# IRDA-piHAT.net
KiCad netlist of a schematic drawn in EAGLE
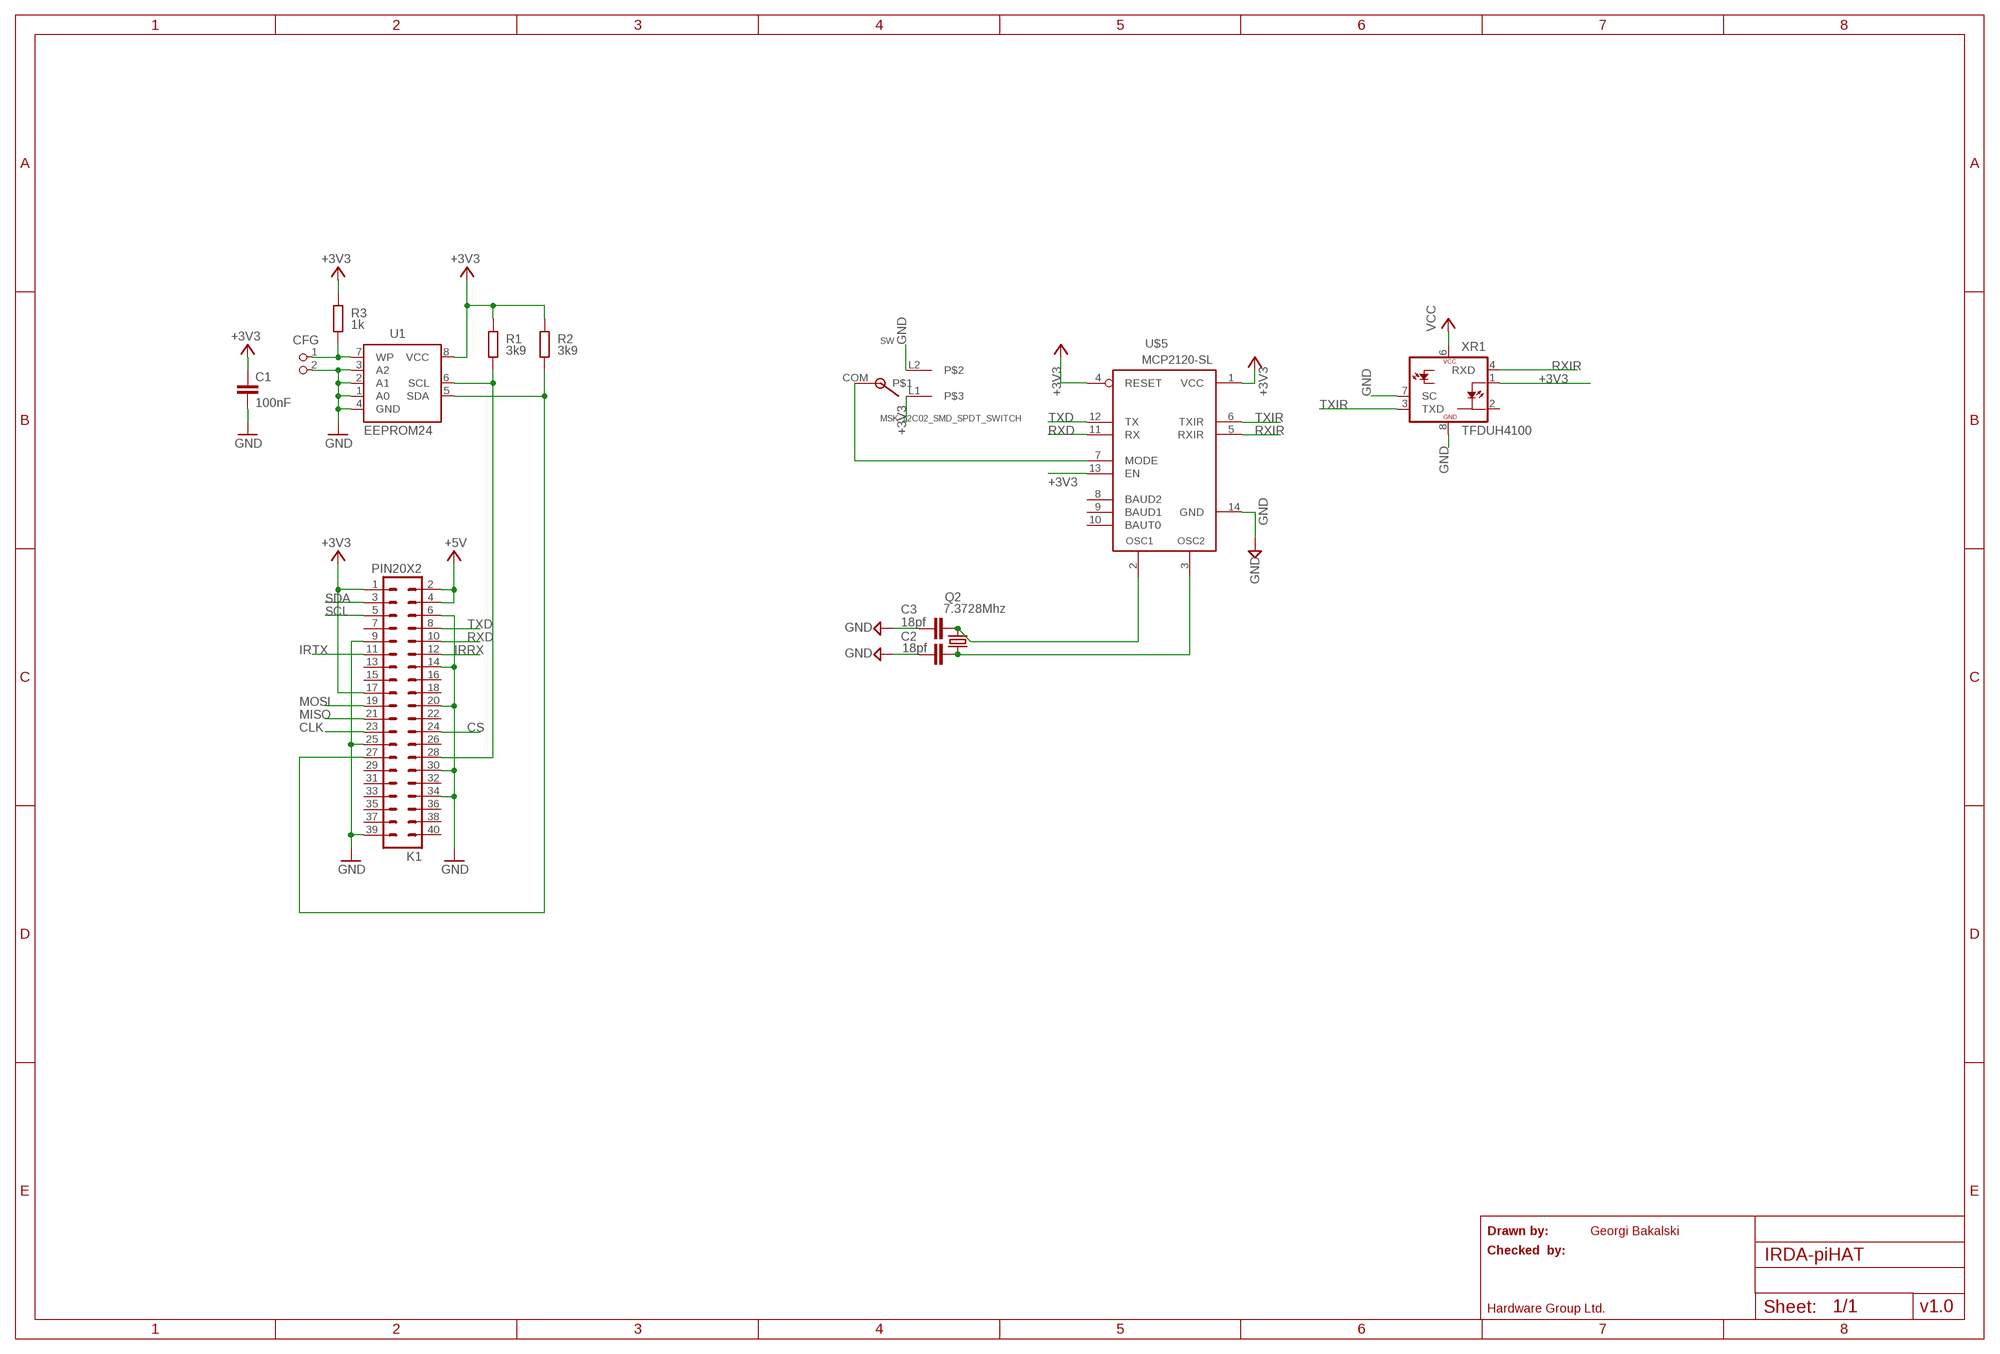
[diagram p0: schematic, sheet 1]

(export (version "E")
  (design (tool "Eeschema 10.0.6"))
  (components
    (comp (ref "C1")
      (value "100nF")
      (footprint "eagle-import:C0805K")
      (libsource (lib "eagle-import") (part "C-EUC0805K"))
    )
    (comp (ref "C2")
      (value "18pf")
      (footprint "eagle-import:C603")
      (libsource (lib "eagle-import") (part "CAPC603"))
    )
    (comp (ref "C3")
      (value "18pf")
      (footprint "eagle-import:C603")
      (libsource (lib "eagle-import") (part "CAPC603"))
    )
    (comp (ref "CFG")
      (value "PIN2_100")
      (footprint "eagle-import:PIN_W_2")
      (libsource (lib "eagle-import") (part "PIN2_100"))
    )
    (comp (ref "K1")
      (value "PIN20X2")
      (footprint "eagle-import:PIN_20X2")
      (libsource (lib "eagle-import") (part "PIN20X2"))
    )
    (comp (ref "Q2")
      (value "7.3728Mhz")
      (footprint "eagle-import:HC49UP")
      (libsource (lib "eagle-import") (part "CRYSTALHC49UP"))
    )
    (comp (ref "R1")
      (value "3k9")
      (footprint "eagle-import:M0805")
      (fields (field (name "TOLERANCE") "5%"))
      (libsource (lib "eagle-import") (part "R-EU_M0805"))
    )
    (comp (ref "R2")
      (value "3k9")
      (footprint "eagle-import:M0805")
      (fields (field (name "TOLERANCE") "5%"))
      (libsource (lib "eagle-import") (part "R-EU_M0805"))
    )
    (comp (ref "R3")
      (value "1k")
      (footprint "eagle-import:M0805")
      (fields (field (name "TOLERANCE") "5%"))
      (libsource (lib "eagle-import") (part "R-EU_M0805"))
    )
    (comp (ref "SW")
      (value "MSK-12C02_SMD_SPDT_SWITCH")
      (footprint "eagle-import:MSK-12C02")
      (libsource (lib "eagle-import") (part "MSK-12C02_SMD_SPDT_SWITCH"))
    )
    (comp (ref "U$5")
      (value "MCP2120-SL")
      (footprint "eagle-import:SO-14")
      (libsource (lib "eagle-import") (part "MCP2120-SL"))
    )
    (comp (ref "U1")
      (value "EEPROM24")
      (footprint "eagle-import:SOIC8")
      (libsource (lib "eagle-import") (part "EEPROM24"))
    )
    (comp (ref "XR1")
      (value "TFDUH4100")
      (footprint "eagle-import:TFDU4-HOR")
      (fields (field (name "MPN") "TFDU4101-TT3"))
      (libsource (lib "eagle-import") (part "TFD?4100UH"))
    )
  )
  (nets
    (net (code "1") (name "+3V3") (class "Default")
      (node (ref "C1") (pin "1") (pinfunction "1_1") (pintype "passive"))
      (node (ref "K1") (pin "1") (pinfunction "1_1") (pintype "passive"))
      (node (ref "K1") (pin "17") (pinfunction "17_17") (pintype "passive"))
      (node (ref "R1") (pin "2") (pinfunction "2_2") (pintype "passive"))
      (node (ref "R2") (pin "2") (pinfunction "2_2") (pintype "passive"))
      (node (ref "R3") (pin "2") (pinfunction "2_2") (pintype "passive"))
      (node (ref "SW") (pin "L1") (pinfunction "P$3_L1") (pintype "bidirectional"))
      (node (ref "U$5") (pin "1") (pinfunction "VCC_1") (pintype "power_in"))
      (node (ref "U$5") (pin "13") (pinfunction "EN_13") (pintype "input"))
      (node (ref "U$5") (pin "4") (pinfunction "RESET_4") (pintype "bidirectional"))
      (node (ref "U1") (pin "8") (pinfunction "VCC_8") (pintype "power_in"))
      (node (ref "XR1") (pin "1") (pinfunction "IRED-A_1") (pintype "passive"))
      (node (ref "XR1") (pin "6") (pinfunction "VCC_6") (pintype "power_in"))
    )
    (net (code "2") (name "+5V") (class "Default")
      (node (ref "K1") (pin "2") (pinfunction "2_2") (pintype "passive"))
      (node (ref "K1") (pin "4") (pinfunction "4_4") (pintype "passive"))
    )
    (net (code "3") (name "/CLK") (class "Default")
      (node (ref "K1") (pin "23") (pinfunction "23_23") (pintype "passive"))
    )
    (net (code "4") (name "/CS") (class "Default")
      (node (ref "K1") (pin "24") (pinfunction "24_24") (pintype "passive"))
    )
    (net (code "5") (name "/IRRX") (class "Default")
      (node (ref "K1") (pin "12") (pinfunction "12_12") (pintype "passive"))
    )
    (net (code "6") (name "/IRTX") (class "Default")
      (node (ref "K1") (pin "11") (pinfunction "11_11") (pintype "passive"))
    )
    (net (code "7") (name "/MISO") (class "Default")
      (node (ref "K1") (pin "21") (pinfunction "21_21") (pintype "passive"))
    )
    (net (code "8") (name "/MOSI") (class "Default")
      (node (ref "K1") (pin "19") (pinfunction "19_19") (pintype "passive"))
    )
    (net (code "9") (name "/RXD") (class "Default")
      (node (ref "K1") (pin "10") (pinfunction "10_10") (pintype "passive"))
      (node (ref "U$5") (pin "11") (pinfunction "RX_11") (pintype "output"))
    )
    (net (code "10") (name "/RXIR") (class "Default")
      (node (ref "U$5") (pin "5") (pinfunction "RXIR_5") (pintype "input"))
      (node (ref "XR1") (pin "4") (pinfunction "RXD_4") (pintype "output"))
    )
    (net (code "11") (name "/SCL") (class "Default")
      (node (ref "K1") (pin "5") (pinfunction "5_5") (pintype "passive"))
    )
    (net (code "12") (name "/SDA") (class "Default")
      (node (ref "K1") (pin "3") (pinfunction "3_3") (pintype "passive"))
    )
    (net (code "13") (name "/TXD") (class "Default")
      (node (ref "K1") (pin "8") (pinfunction "8_8") (pintype "passive"))
      (node (ref "U$5") (pin "12") (pinfunction "TX_12") (pintype "input"))
    )
    (net (code "14") (name "/TXIR") (class "Default")
      (node (ref "U$5") (pin "6") (pinfunction "TXIR_6") (pintype "output"))
      (node (ref "XR1") (pin "3") (pinfunction "TXD_3") (pintype "input"))
    )
    (net (code "15") (name "GND") (class "Default")
      (node (ref "C1") (pin "2") (pinfunction "2_2") (pintype "passive"))
      (node (ref "C2") (pin "2") (pinfunction "2_2") (pintype "passive"))
      (node (ref "C3") (pin "2") (pinfunction "2_2") (pintype "passive"))
      (node (ref "CFG") (pin "2") (pinfunction "2_2") (pintype "passive"))
      (node (ref "K1") (pin "14") (pinfunction "14_14") (pintype "passive"))
      (node (ref "K1") (pin "20") (pinfunction "20_20") (pintype "passive"))
      (node (ref "K1") (pin "25") (pinfunction "25_25") (pintype "passive"))
      (node (ref "K1") (pin "30") (pinfunction "30_30") (pintype "passive"))
      (node (ref "K1") (pin "34") (pinfunction "34_34") (pintype "passive"))
      (node (ref "K1") (pin "39") (pinfunction "39_39") (pintype "passive"))
      (node (ref "K1") (pin "6") (pinfunction "6_6") (pintype "passive"))
      (node (ref "K1") (pin "9") (pinfunction "9_9") (pintype "passive"))
      (node (ref "SW") (pin "L2") (pinfunction "P$2_L2") (pintype "bidirectional"))
      (node (ref "U$5") (pin "14") (pinfunction "GND_14") (pintype "power_in"))
      (node (ref "U1") (pin "1") (pinfunction "A0_1") (pintype "input"))
      (node (ref "U1") (pin "2") (pinfunction "A1_2") (pintype "input"))
      (node (ref "U1") (pin "3") (pinfunction "A2_3") (pintype "input"))
      (node (ref "U1") (pin "4") (pinfunction "GND_4") (pintype "power_in"))
      (node (ref "XR1") (pin "7") (pinfunction "SC_7") (pintype "input"))
      (node (ref "XR1") (pin "8") (pinfunction "GND_8") (pintype "power_in"))
    )
    (net (code "16") (name "Net-(SW-P$1)") (class "Default")
      (node (ref "SW") (pin "COM") (pinfunction "P$1_COM") (pintype "bidirectional"))
      (node (ref "U$5") (pin "7") (pinfunction "MODE_7") (pintype "input"))
    )
    (net (code "17") (name "Net-(U$5-OSC1)") (class "Default")
      (node (ref "C3") (pin "1") (pinfunction "1_1") (pintype "passive"))
      (node (ref "Q2") (pin "2") (pinfunction "2_2") (pintype "passive"))
      (node (ref "U$5") (pin "2") (pinfunction "OSC1_2") (pintype "input"))
    )
    (net (code "18") (name "Net-(U$5-OSC2)") (class "Default")
      (node (ref "C2") (pin "1") (pinfunction "1_1") (pintype "passive"))
      (node (ref "Q2") (pin "1") (pinfunction "1_1") (pintype "passive"))
      (node (ref "U$5") (pin "3") (pinfunction "OSC2_3") (pintype "output"))
    )
    (net (code "19") (name "Net-(U1-SCL)") (class "Default")
      (node (ref "K1") (pin "28") (pinfunction "28_28") (pintype "passive"))
      (node (ref "R1") (pin "1") (pinfunction "1_1") (pintype "passive"))
      (node (ref "U1") (pin "6") (pinfunction "SCL_6") (pintype "input"))
    )
    (net (code "20") (name "Net-(U1-SDA)") (class "Default")
      (node (ref "K1") (pin "27") (pinfunction "27_27") (pintype "passive"))
      (node (ref "R2") (pin "1") (pinfunction "1_1") (pintype "passive"))
      (node (ref "U1") (pin "5") (pinfunction "SDA_5") (pintype "bidirectional"))
    )
    (net (code "21") (name "Net-(U1-WP)") (class "Default")
      (node (ref "CFG") (pin "1") (pinfunction "1_1") (pintype "passive"))
      (node (ref "R3") (pin "1") (pinfunction "1_1") (pintype "passive"))
      (node (ref "U1") (pin "7") (pinfunction "WP_7") (pintype "input"))
    )
    (net (code "22") (name "unconnected-(K1-Pad7)") (class "Default")
      (node (ref "K1") (pin "7") (pinfunction "7_7") (pintype "passive"))
    )
    (net (code "23") (name "unconnected-(K1-Pad13)") (class "Default")
      (node (ref "K1") (pin "13") (pinfunction "13_13") (pintype "passive"))
    )
    (net (code "24") (name "unconnected-(K1-Pad15)") (class "Default")
      (node (ref "K1") (pin "15") (pinfunction "15_15") (pintype "passive"))
    )
    (net (code "25") (name "unconnected-(K1-Pad16)") (class "Default")
      (node (ref "K1") (pin "16") (pinfunction "16_16") (pintype "passive"))
    )
    (net (code "26") (name "unconnected-(K1-Pad18)") (class "Default")
      (node (ref "K1") (pin "18") (pinfunction "18_18") (pintype "passive"))
    )
    (net (code "27") (name "unconnected-(K1-Pad22)") (class "Default")
      (node (ref "K1") (pin "22") (pinfunction "22_22") (pintype "passive"))
    )
    (net (code "28") (name "unconnected-(K1-Pad26)") (class "Default")
      (node (ref "K1") (pin "26") (pinfunction "26_26") (pintype "passive"))
    )
    (net (code "29") (name "unconnected-(K1-Pad29)") (class "Default")
      (node (ref "K1") (pin "29") (pinfunction "29_29") (pintype "passive"))
    )
    (net (code "30") (name "unconnected-(K1-Pad31)") (class "Default")
      (node (ref "K1") (pin "31") (pinfunction "31_31") (pintype "passive"))
    )
    (net (code "31") (name "unconnected-(K1-Pad32)") (class "Default")
      (node (ref "K1") (pin "32") (pinfunction "32_32") (pintype "passive"))
    )
    (net (code "32") (name "unconnected-(K1-Pad33)") (class "Default")
      (node (ref "K1") (pin "33") (pinfunction "33_33") (pintype "passive"))
    )
    (net (code "33") (name "unconnected-(K1-Pad35)") (class "Default")
      (node (ref "K1") (pin "35") (pinfunction "35_35") (pintype "passive"))
    )
    (net (code "34") (name "unconnected-(K1-Pad36)") (class "Default")
      (node (ref "K1") (pin "36") (pinfunction "36_36") (pintype "passive"))
    )
    (net (code "35") (name "unconnected-(K1-Pad37)") (class "Default")
      (node (ref "K1") (pin "37") (pinfunction "37_37") (pintype "passive"))
    )
    (net (code "36") (name "unconnected-(K1-Pad38)") (class "Default")
      (node (ref "K1") (pin "38") (pinfunction "38_38") (pintype "passive"))
    )
    (net (code "37") (name "unconnected-(K1-Pad40)") (class "Default")
      (node (ref "K1") (pin "40") (pinfunction "40_40") (pintype "passive"))
    )
    (net (code "38") (name "unconnected-(U$5-BAUD1-Pad9)") (class "Default")
      (node (ref "U$5") (pin "9") (pinfunction "BAUD1_9") (pintype "input"))
    )
    (net (code "39") (name "unconnected-(U$5-BAUD2-Pad8)") (class "Default")
      (node (ref "U$5") (pin "8") (pinfunction "BAUD2_8") (pintype "input"))
    )
    (net (code "40") (name "unconnected-(U$5-BAUT0-Pad10)") (class "Default")
      (node (ref "U$5") (pin "10") (pinfunction "BAUT0_10") (pintype "input"))
    )
    (net (code "41") (name "unconnected-(XR1-IRED-C-Pad2)") (class "Default")
      (node (ref "XR1") (pin "2") (pinfunction "IRED-C_2") (pintype "output"))
    )
  )
)
